# LED_Strip_Adapter.net
KiCad netlist of a schematic drawn in EAGLE
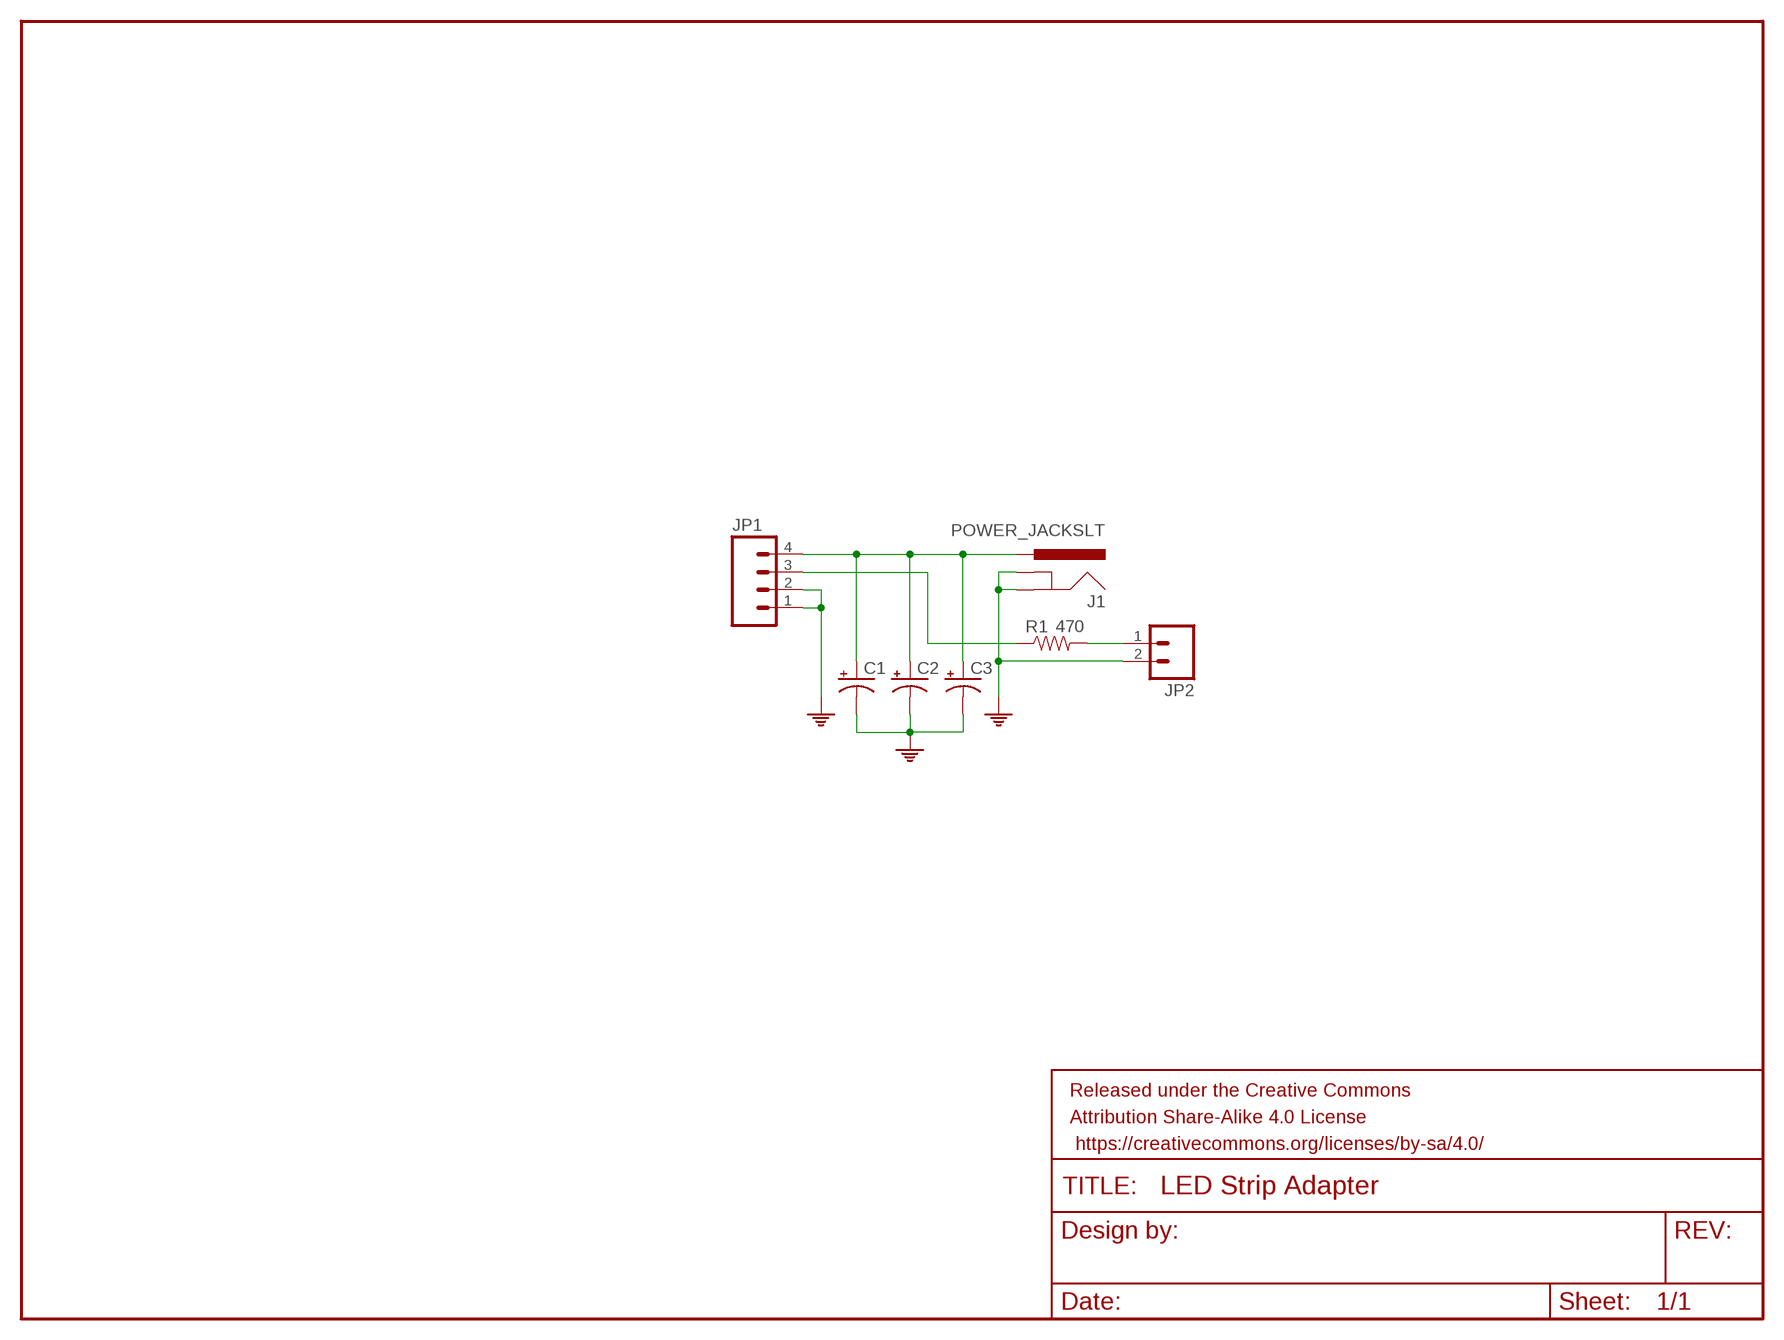
[diagram p0: schematic, sheet 1]

(export (version "E")
  (design (tool "Eeschema 10.0.6"))
  (components
    (comp (ref "C1")
      (value "CAP_POLPTH2")
      (footprint "eagle-import:CPOL-RADIAL-10UF-25V")
      (libsource (lib "eagle-import") (part "CAP_POLPTH2"))
    )
    (comp (ref "C2")
      (value "CAP_POLPTH2")
      (footprint "eagle-import:CPOL-RADIAL-10UF-25V")
      (libsource (lib "eagle-import") (part "CAP_POLPTH2"))
    )
    (comp (ref "C3")
      (value "CAP_POLPTH2")
      (footprint "eagle-import:CPOL-RADIAL-10UF-25V")
      (libsource (lib "eagle-import") (part "CAP_POLPTH2"))
    )
    (comp (ref "FRAME1")
      (value "FRAME-LETTER")
      (footprint "eagle-import:CREATIVE_COMMONS")
      (libsource (lib "eagle-import") (part "FRAME-LETTER"))
    )
    (comp (ref "J1")
      (value "POWER_JACKSLT")
      (footprint "eagle-import:POWER_JACK_SLOT")
      (libsource (lib "eagle-import") (part "POWER_JACKSLT"))
    )
    (comp (ref "JP1")
      (value "M04LOCK_LONGPADS")
      (footprint "eagle-import:1X04_LOCK_LONGPADS")
      (libsource (lib "eagle-import") (part "M04LOCK_LONGPADS"))
    )
    (comp (ref "JP2")
      (value "M02LOCK_LONGPADS")
      (footprint "eagle-import:1X02_LOCK_LONGPADS")
      (libsource (lib "eagle-import") (part "M02LOCK_LONGPADS"))
    )
    (comp (ref "R1")
      (value "470")
      (footprint "eagle-import:1206")
      (libsource (lib "eagle-import") (part "RESISTOR1206"))
    )
  )
  (nets
    (net (code "1") (name "GND_US") (class "Default")
      (node (ref "C1") (pin "2") (pinfunction "-_2") (pintype "passive"))
      (node (ref "C2") (pin "2") (pinfunction "-_2") (pintype "passive"))
      (node (ref "C3") (pin "2") (pinfunction "-_2") (pintype "passive"))
      (node (ref "J1") (pin "GND@1") (pinfunction "GNDBREAK_GND@1") (pintype "bidirectional"))
      (node (ref "J1") (pin "GND@2") (pinfunction "GND_GND@2") (pintype "bidirectional"))
      (node (ref "JP1") (pin "1") (pinfunction "1_1") (pintype "passive"))
      (node (ref "JP1") (pin "2") (pinfunction "2_2") (pintype "passive"))
      (node (ref "JP2") (pin "2") (pinfunction "2_2") (pintype "passive"))
    )
    (net (code "2") (name "Net-(C1-+)") (class "Default")
      (node (ref "C1") (pin "1") (pinfunction "+_1") (pintype "passive"))
      (node (ref "C2") (pin "1") (pinfunction "+_1") (pintype "passive"))
      (node (ref "C3") (pin "1") (pinfunction "+_1") (pintype "passive"))
      (node (ref "J1") (pin "PWR") (pinfunction "PWR_PWR") (pintype "bidirectional"))
      (node (ref "JP1") (pin "4") (pinfunction "4_4") (pintype "passive"))
    )
    (net (code "3") (name "Net-(JP1-Pad3)") (class "Default")
      (node (ref "JP1") (pin "3") (pinfunction "3_3") (pintype "passive"))
      (node (ref "R1") (pin "1") (pinfunction "1_1") (pintype "passive"))
    )
    (net (code "4") (name "Net-(JP2-Pad1)") (class "Default")
      (node (ref "JP2") (pin "1") (pinfunction "1_1") (pintype "passive"))
      (node (ref "R1") (pin "2") (pinfunction "2_2") (pintype "passive"))
    )
  )
)
